# smartsensor_powered_jig.net
KiCad netlist of a schematic drawn in EAGLE
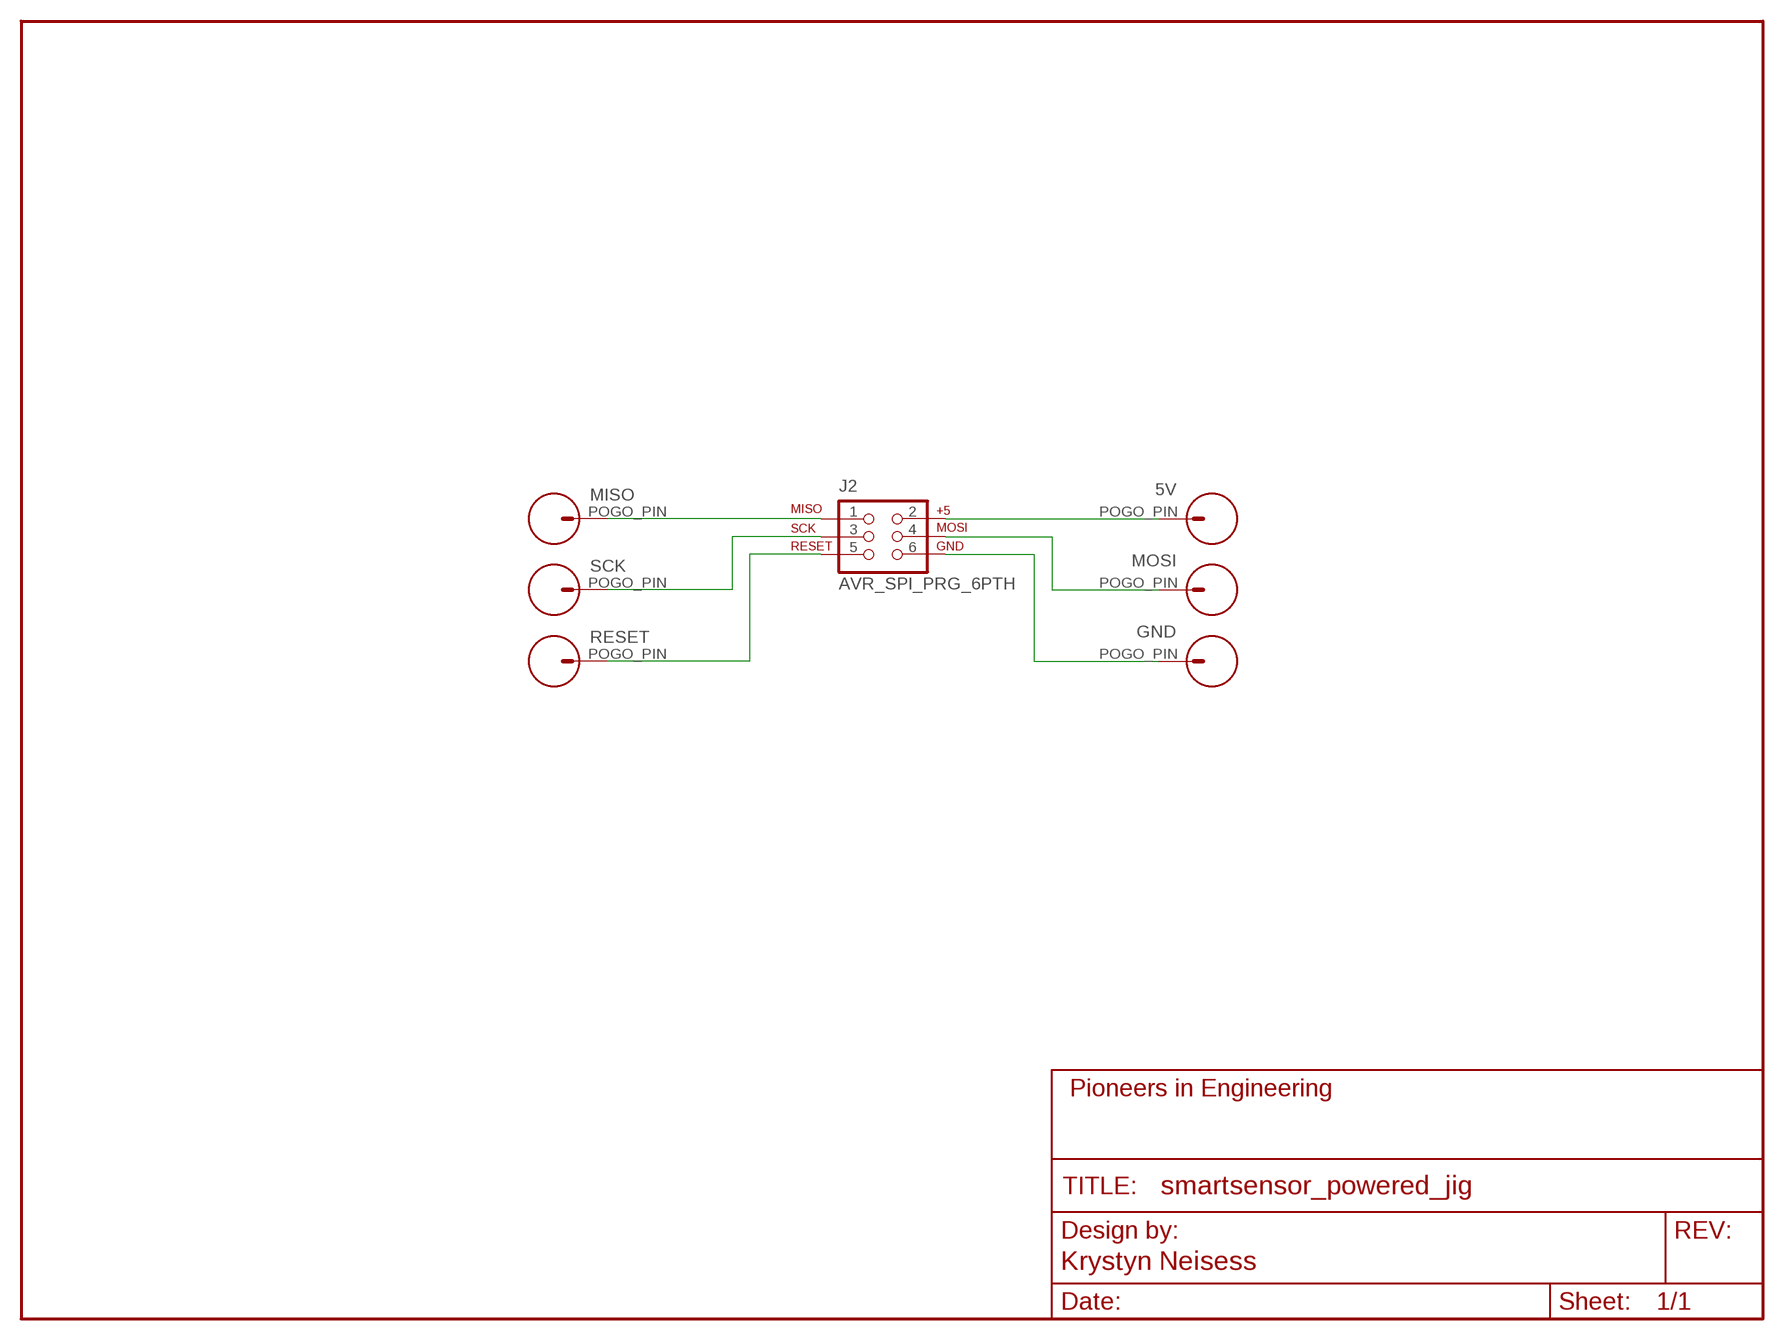
[diagram p0: schematic, sheet 1]

(export (version "E")
  (design (tool "Eeschema 10.0.6"))
  (components
    (comp (ref "5V")
      (value "POGO_PIN")
      (footprint "eagle-import:POGO_PIN_394")
      (libsource (lib "eagle-import") (part "POGO_PIN"))
    )
    (comp (ref "GND")
      (value "POGO_PIN")
      (footprint "eagle-import:POGO_PIN_394")
      (libsource (lib "eagle-import") (part "POGO_PIN"))
    )
    (comp (ref "J2")
      (value "AVR_SPI_PRG_6PTH")
      (footprint "eagle-import:2X3")
      (libsource (lib "eagle-import") (part "AVR_SPI_PRG_6PTH"))
    )
    (comp (ref "MISO")
      (value "POGO_PIN")
      (footprint "eagle-import:POGO_PIN_394")
      (libsource (lib "eagle-import") (part "POGO_PIN"))
    )
    (comp (ref "MOSI")
      (value "POGO_PIN")
      (footprint "eagle-import:POGO_PIN_394")
      (libsource (lib "eagle-import") (part "POGO_PIN"))
    )
    (comp (ref "RESET")
      (value "POGO_PIN")
      (footprint "eagle-import:POGO_PIN_394")
      (libsource (lib "eagle-import") (part "POGO_PIN"))
    )
    (comp (ref "SCK")
      (value "POGO_PIN")
      (footprint "eagle-import:POGO_PIN_394")
      (libsource (lib "eagle-import") (part "POGO_PIN"))
    )
  )
  (nets
    (net (code "1") (name "Net-(5V-P$1)") (class "Default")
      (node (ref "5V") (pin "POGO_PIN") (pinfunction "P$1_POGO_PIN") (pintype "bidirectional"))
      (node (ref "J2") (pin "2") (pinfunction "2_2") (pintype "passive"))
    )
    (net (code "2") (name "Net-(GND-P$1)") (class "Default")
      (node (ref "GND") (pin "POGO_PIN") (pinfunction "P$1_POGO_PIN") (pintype "bidirectional"))
      (node (ref "J2") (pin "6") (pinfunction "6_6") (pintype "passive"))
    )
    (net (code "3") (name "Net-(MISO-P$1)") (class "Default")
      (node (ref "J2") (pin "1") (pinfunction "1_1") (pintype "passive"))
      (node (ref "MISO") (pin "POGO_PIN") (pinfunction "P$1_POGO_PIN") (pintype "bidirectional"))
    )
    (net (code "4") (name "Net-(MOSI-P$1)") (class "Default")
      (node (ref "J2") (pin "4") (pinfunction "4_4") (pintype "passive"))
      (node (ref "MOSI") (pin "POGO_PIN") (pinfunction "P$1_POGO_PIN") (pintype "bidirectional"))
    )
    (net (code "5") (name "Net-(RESET-P$1)") (class "Default")
      (node (ref "J2") (pin "5") (pinfunction "5_5") (pintype "passive"))
      (node (ref "RESET") (pin "POGO_PIN") (pinfunction "P$1_POGO_PIN") (pintype "bidirectional"))
    )
    (net (code "6") (name "Net-(SCK-P$1)") (class "Default")
      (node (ref "J2") (pin "3") (pinfunction "3_3") (pintype "passive"))
      (node (ref "SCK") (pin "POGO_PIN") (pinfunction "P$1_POGO_PIN") (pintype "bidirectional"))
    )
  )
)
